# 8x8matrix.net
KiCad netlist of a schematic drawn in EAGLE
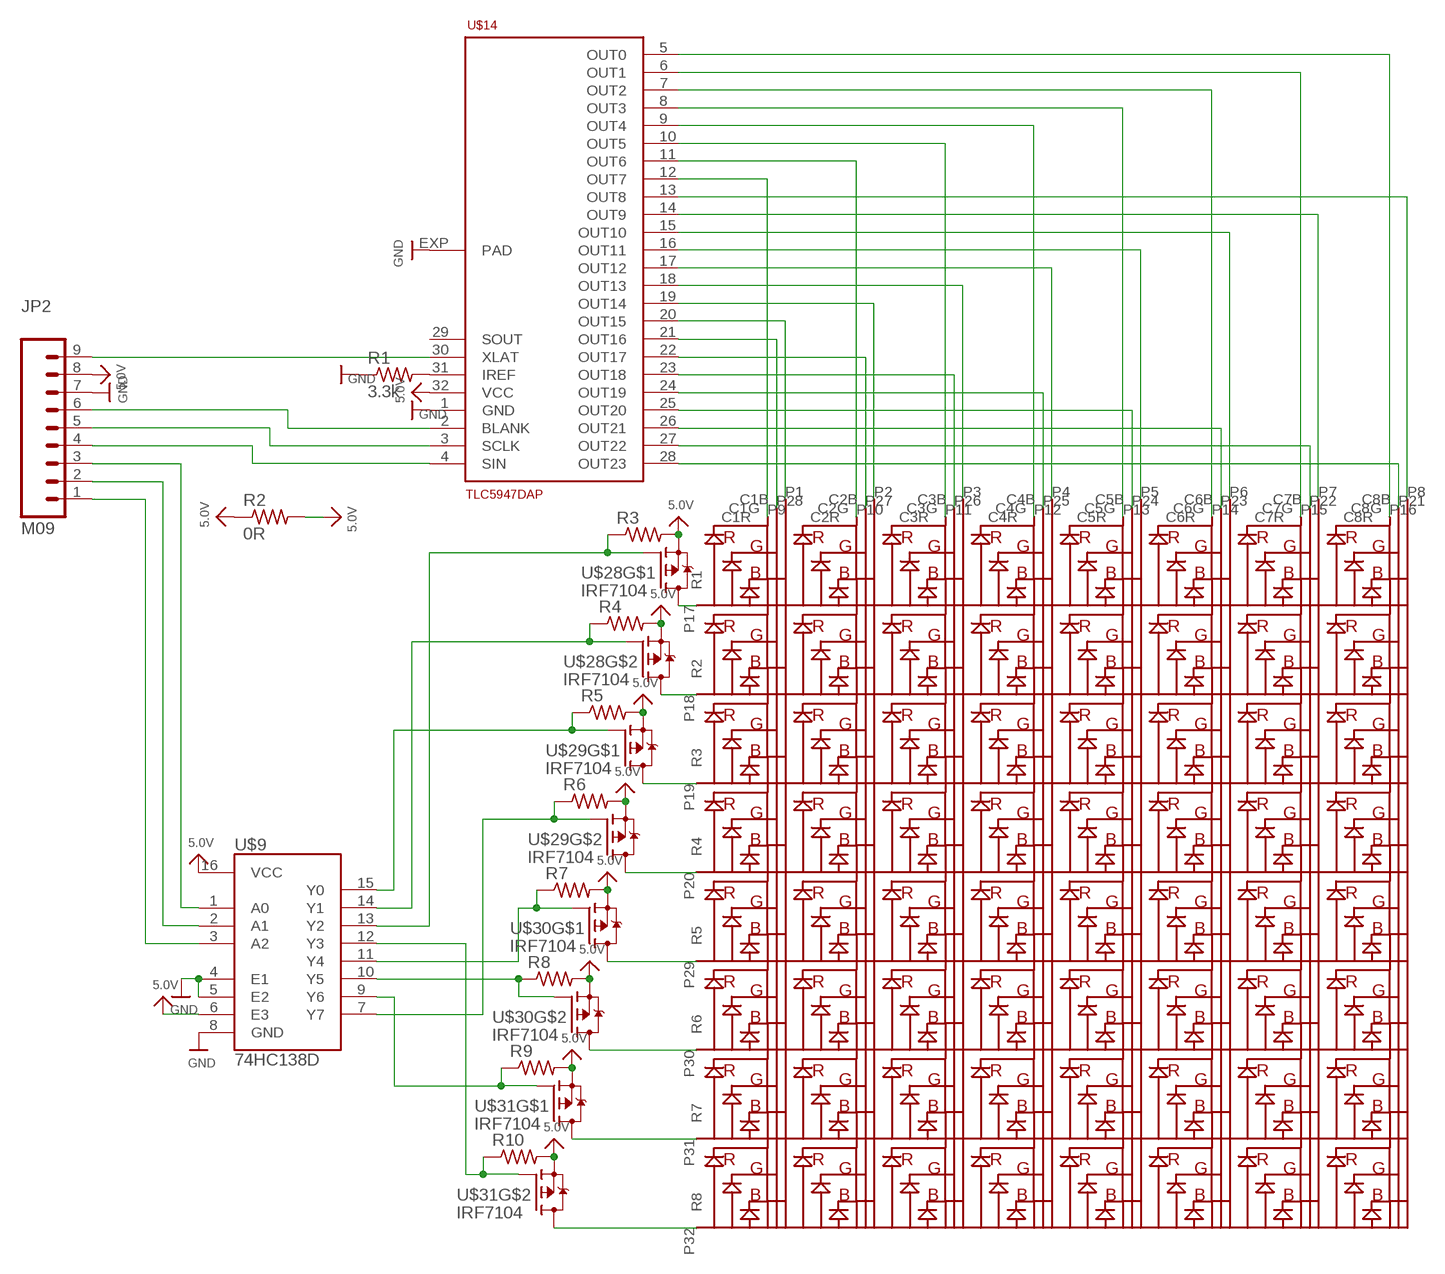
[diagram p0: schematic, sheet 1]

(export (version "E")
  (design (tool "Eeschema 10.0.6"))
  (components
    (comp (ref "JP2")
      (value "M09")
      (footprint "eagle-import:1X09")
      (libsource (lib "eagle-import") (part "M09"))
    )
    (comp (ref "R1")
      (value "3.3k")
      (footprint "eagle-import:R0805")
      (libsource (lib "eagle-import") (part "R-US_R0805"))
    )
    (comp (ref "R2")
      (value "0R")
      (footprint "eagle-import:M1206")
      (libsource (lib "eagle-import") (part "R-US_M1206"))
    )
    (comp (ref "R3")
      (value "R-US_R0805")
      (footprint "eagle-import:R0805")
      (libsource (lib "eagle-import") (part "R-US_R0805"))
    )
    (comp (ref "R4")
      (value "R-US_R0805")
      (footprint "eagle-import:R0805")
      (libsource (lib "eagle-import") (part "R-US_R0805"))
    )
    (comp (ref "R5")
      (value "R-US_R0805")
      (footprint "eagle-import:R0805")
      (libsource (lib "eagle-import") (part "R-US_R0805"))
    )
    (comp (ref "R6")
      (value "R-US_R0805")
      (footprint "eagle-import:R0805")
      (libsource (lib "eagle-import") (part "R-US_R0805"))
    )
    (comp (ref "R7")
      (value "R-US_R0805")
      (footprint "eagle-import:R0805")
      (libsource (lib "eagle-import") (part "R-US_R0805"))
    )
    (comp (ref "R8")
      (value "R-US_R0805")
      (footprint "eagle-import:R0805")
      (libsource (lib "eagle-import") (part "R-US_R0805"))
    )
    (comp (ref "R9")
      (value "R-US_R0805")
      (footprint "eagle-import:R0805")
      (libsource (lib "eagle-import") (part "R-US_R0805"))
    )
    (comp (ref "R10")
      (value "R-US_R0805")
      (footprint "eagle-import:R0805")
      (libsource (lib "eagle-import") (part "R-US_R0805"))
    )
    (comp (ref "U$1")
      (value "GTM2088ARGB")
      (footprint "eagle-import:8X8MATRIX")
      (libsource (lib "eagle-import") (part "GTM2088ARGB"))
    )
    (comp (ref "U$9")
      (value "74HC138D")
      (footprint "eagle-import:SO-16")
      (libsource (lib "eagle-import") (part "74HC138D"))
    )
    (comp (ref "U$14")
      (value "TLC5947DAP")
      (footprint "eagle-import:HTSSOP32DAP")
      (libsource (lib "eagle-import") (part "TLC5947DAP"))
    )
    (comp (ref "U$28")
      (value "IRF7104")
      (footprint "eagle-import:SOIC8")
      (libsource (lib "eagle-import") (part "IRF7104"))
    )
    (comp (ref "U$29")
      (value "IRF7104")
      (footprint "eagle-import:SOIC8")
      (libsource (lib "eagle-import") (part "IRF7104"))
    )
    (comp (ref "U$30")
      (value "IRF7104")
      (footprint "eagle-import:SOIC8")
      (libsource (lib "eagle-import") (part "IRF7104"))
    )
    (comp (ref "U$31")
      (value "IRF7104")
      (footprint "eagle-import:SOIC8")
      (libsource (lib "eagle-import") (part "IRF7104"))
    )
  )
  (nets
    (net (code "1") (name "5.0V") (class "Default")
      (node (ref "JP2") (pin "8") (pinfunction "8_8") (pintype "passive"))
      (node (ref "R10") (pin "2") (pinfunction "2_2") (pintype "passive"))
      (node (ref "R2") (pin "1") (pinfunction "1_1") (pintype "passive"))
      (node (ref "R2") (pin "2") (pinfunction "2_2") (pintype "passive"))
      (node (ref "R3") (pin "2") (pinfunction "2_2") (pintype "passive"))
      (node (ref "R4") (pin "2") (pinfunction "2_2") (pintype "passive"))
      (node (ref "R5") (pin "2") (pinfunction "2_2") (pintype "passive"))
      (node (ref "R6") (pin "2") (pinfunction "2_2") (pintype "passive"))
      (node (ref "R7") (pin "2") (pinfunction "2_2") (pintype "passive"))
      (node (ref "R8") (pin "2") (pinfunction "2_2") (pintype "passive"))
      (node (ref "R9") (pin "2") (pinfunction "2_2") (pintype "passive"))
      (node (ref "U$14") (pin "32") (pinfunction "VCC_32") (pintype "bidirectional"))
      (node (ref "U$28") (pin "1") (pinfunction "S_1") (pintype "passive"))
      (node (ref "U$28") (pin "3") (pinfunction "S_3") (pintype "passive"))
      (node (ref "U$29") (pin "1") (pinfunction "S_1") (pintype "passive"))
      (node (ref "U$29") (pin "3") (pinfunction "S_3") (pintype "passive"))
      (node (ref "U$30") (pin "1") (pinfunction "S_1") (pintype "passive"))
      (node (ref "U$30") (pin "3") (pinfunction "S_3") (pintype "passive"))
      (node (ref "U$31") (pin "1") (pinfunction "S_1") (pintype "passive"))
      (node (ref "U$31") (pin "3") (pinfunction "S_3") (pintype "passive"))
      (node (ref "U$9") (pin "16") (pinfunction "VCC_16") (pintype "bidirectional"))
      (node (ref "U$9") (pin "6") (pinfunction "E3_6") (pintype "bidirectional"))
    )
    (net (code "2") (name "GND") (class "Default")
      (node (ref "JP2") (pin "7") (pinfunction "7_7") (pintype "passive"))
      (node (ref "R1") (pin "1") (pinfunction "1_1") (pintype "passive"))
      (node (ref "U$14") (pin "1") (pinfunction "GND_1") (pintype "bidirectional"))
      (node (ref "U$14") (pin "EXP") (pinfunction "PAD_EXP") (pintype "bidirectional"))
      (node (ref "U$9") (pin "4") (pinfunction "E1_4") (pintype "bidirectional"))
      (node (ref "U$9") (pin "5") (pinfunction "E2_5") (pintype "bidirectional"))
      (node (ref "U$9") (pin "8") (pinfunction "GND_8") (pintype "bidirectional"))
    )
    (net (code "3") (name "Net-(U$1-C1B)") (class "Default")
      (node (ref "U$1") (pin "P1") (pinfunction "C1B_P1") (pintype "bidirectional"))
      (node (ref "U$14") (pin "20") (pinfunction "OUT15_20") (pintype "bidirectional"))
    )
    (net (code "4") (name "Net-(U$1-C1G)") (class "Default")
      (node (ref "U$1") (pin "P28") (pinfunction "C1G_P28") (pintype "bidirectional"))
      (node (ref "U$14") (pin "21") (pinfunction "OUT16_21") (pintype "bidirectional"))
    )
    (net (code "5") (name "Net-(U$1-C1R)") (class "Default")
      (node (ref "U$1") (pin "P9") (pinfunction "C1R_P9") (pintype "bidirectional"))
      (node (ref "U$14") (pin "12") (pinfunction "OUT7_12") (pintype "bidirectional"))
    )
    (net (code "6") (name "Net-(U$1-C2B)") (class "Default")
      (node (ref "U$1") (pin "P2") (pinfunction "C2B_P2") (pintype "bidirectional"))
      (node (ref "U$14") (pin "19") (pinfunction "OUT14_19") (pintype "bidirectional"))
    )
    (net (code "7") (name "Net-(U$1-C2G)") (class "Default")
      (node (ref "U$1") (pin "P27") (pinfunction "C2G_P27") (pintype "bidirectional"))
      (node (ref "U$14") (pin "22") (pinfunction "OUT17_22") (pintype "bidirectional"))
    )
    (net (code "8") (name "Net-(U$1-C2R)") (class "Default")
      (node (ref "U$1") (pin "P10") (pinfunction "C2R_P10") (pintype "bidirectional"))
      (node (ref "U$14") (pin "11") (pinfunction "OUT6_11") (pintype "bidirectional"))
    )
    (net (code "9") (name "Net-(U$1-C3B)") (class "Default")
      (node (ref "U$1") (pin "P3") (pinfunction "C3B_P3") (pintype "bidirectional"))
      (node (ref "U$14") (pin "18") (pinfunction "OUT13_18") (pintype "bidirectional"))
    )
    (net (code "10") (name "Net-(U$1-C3G)") (class "Default")
      (node (ref "U$1") (pin "P26") (pinfunction "C3G_P26") (pintype "bidirectional"))
      (node (ref "U$14") (pin "23") (pinfunction "OUT18_23") (pintype "bidirectional"))
    )
    (net (code "11") (name "Net-(U$1-C3R)") (class "Default")
      (node (ref "U$1") (pin "P11") (pinfunction "C3R_P11") (pintype "bidirectional"))
      (node (ref "U$14") (pin "10") (pinfunction "OUT5_10") (pintype "bidirectional"))
    )
    (net (code "12") (name "Net-(U$1-C4B)") (class "Default")
      (node (ref "U$1") (pin "P4") (pinfunction "C4B_P4") (pintype "bidirectional"))
      (node (ref "U$14") (pin "17") (pinfunction "OUT12_17") (pintype "bidirectional"))
    )
    (net (code "13") (name "Net-(U$1-C4G)") (class "Default")
      (node (ref "U$1") (pin "P25") (pinfunction "C4G_P25") (pintype "bidirectional"))
      (node (ref "U$14") (pin "24") (pinfunction "OUT19_24") (pintype "bidirectional"))
    )
    (net (code "14") (name "Net-(U$1-C4R)") (class "Default")
      (node (ref "U$1") (pin "P12") (pinfunction "C4R_P12") (pintype "bidirectional"))
      (node (ref "U$14") (pin "9") (pinfunction "OUT4_9") (pintype "bidirectional"))
    )
    (net (code "15") (name "Net-(U$1-C5B)") (class "Default")
      (node (ref "U$1") (pin "P5") (pinfunction "C5B_P5") (pintype "bidirectional"))
      (node (ref "U$14") (pin "16") (pinfunction "OUT11_16") (pintype "bidirectional"))
    )
    (net (code "16") (name "Net-(U$1-C5G)") (class "Default")
      (node (ref "U$1") (pin "P24") (pinfunction "C5G_P24") (pintype "bidirectional"))
      (node (ref "U$14") (pin "25") (pinfunction "OUT20_25") (pintype "bidirectional"))
    )
    (net (code "17") (name "Net-(U$1-C5R)") (class "Default")
      (node (ref "U$1") (pin "P13") (pinfunction "C5R_P13") (pintype "bidirectional"))
      (node (ref "U$14") (pin "8") (pinfunction "OUT3_8") (pintype "bidirectional"))
    )
    (net (code "18") (name "Net-(U$1-C6B)") (class "Default")
      (node (ref "U$1") (pin "P6") (pinfunction "C6B_P6") (pintype "bidirectional"))
      (node (ref "U$14") (pin "15") (pinfunction "OUT10_15") (pintype "bidirectional"))
    )
    (net (code "19") (name "Net-(U$1-C6G)") (class "Default")
      (node (ref "U$1") (pin "P23") (pinfunction "C6G_P23") (pintype "bidirectional"))
      (node (ref "U$14") (pin "26") (pinfunction "OUT21_26") (pintype "bidirectional"))
    )
    (net (code "20") (name "Net-(U$1-C6R)") (class "Default")
      (node (ref "U$1") (pin "P14") (pinfunction "C6R_P14") (pintype "bidirectional"))
      (node (ref "U$14") (pin "7") (pinfunction "OUT2_7") (pintype "bidirectional"))
    )
    (net (code "21") (name "Net-(U$1-C7B)") (class "Default")
      (node (ref "U$1") (pin "P7") (pinfunction "C7B_P7") (pintype "bidirectional"))
      (node (ref "U$14") (pin "14") (pinfunction "OUT9_14") (pintype "bidirectional"))
    )
    (net (code "22") (name "Net-(U$1-C7G)") (class "Default")
      (node (ref "U$1") (pin "P22") (pinfunction "C7G_P22") (pintype "bidirectional"))
      (node (ref "U$14") (pin "27") (pinfunction "OUT22_27") (pintype "bidirectional"))
    )
    (net (code "23") (name "Net-(U$1-C7R)") (class "Default")
      (node (ref "U$1") (pin "P15") (pinfunction "C7R_P15") (pintype "bidirectional"))
      (node (ref "U$14") (pin "6") (pinfunction "OUT1_6") (pintype "bidirectional"))
    )
    (net (code "24") (name "Net-(U$1-C8B)") (class "Default")
      (node (ref "U$1") (pin "P8") (pinfunction "C8B_P8") (pintype "bidirectional"))
      (node (ref "U$14") (pin "13") (pinfunction "OUT8_13") (pintype "bidirectional"))
    )
    (net (code "25") (name "Net-(U$1-C8G)") (class "Default")
      (node (ref "U$1") (pin "P21") (pinfunction "C8G_P21") (pintype "bidirectional"))
      (node (ref "U$14") (pin "28") (pinfunction "OUT23_28") (pintype "bidirectional"))
    )
    (net (code "26") (name "Net-(U$1-C8R)") (class "Default")
      (node (ref "U$1") (pin "P16") (pinfunction "C8R_P16") (pintype "bidirectional"))
      (node (ref "U$14") (pin "5") (pinfunction "OUT0_5") (pintype "bidirectional"))
    )
    (net (code "27") (name "Net-(U$1-R1)") (class "Default")
      (node (ref "U$1") (pin "P17") (pinfunction "R1_P17") (pintype "bidirectional"))
      (node (ref "U$28") (pin "7") (pinfunction "D_7") (pintype "passive"))
      (node (ref "U$28") (pin "8") (pinfunction "D_8") (pintype "passive"))
    )
    (net (code "28") (name "Net-(U$1-R2)") (class "Default")
      (node (ref "U$1") (pin "P18") (pinfunction "R2_P18") (pintype "bidirectional"))
      (node (ref "U$28") (pin "5") (pinfunction "D_5") (pintype "passive"))
      (node (ref "U$28") (pin "6") (pinfunction "D_6") (pintype "passive"))
    )
    (net (code "29") (name "Net-(U$1-R3)") (class "Default")
      (node (ref "U$1") (pin "P19") (pinfunction "R3_P19") (pintype "bidirectional"))
      (node (ref "U$29") (pin "7") (pinfunction "D_7") (pintype "passive"))
      (node (ref "U$29") (pin "8") (pinfunction "D_8") (pintype "passive"))
    )
    (net (code "30") (name "Net-(U$1-R4)") (class "Default")
      (node (ref "U$1") (pin "P20") (pinfunction "R4_P20") (pintype "bidirectional"))
      (node (ref "U$29") (pin "5") (pinfunction "D_5") (pintype "passive"))
      (node (ref "U$29") (pin "6") (pinfunction "D_6") (pintype "passive"))
    )
    (net (code "31") (name "Net-(U$1-R5)") (class "Default")
      (node (ref "U$1") (pin "P29") (pinfunction "R5_P29") (pintype "bidirectional"))
      (node (ref "U$30") (pin "7") (pinfunction "D_7") (pintype "passive"))
      (node (ref "U$30") (pin "8") (pinfunction "D_8") (pintype "passive"))
    )
    (net (code "32") (name "Net-(U$1-R6)") (class "Default")
      (node (ref "U$1") (pin "P30") (pinfunction "R6_P30") (pintype "bidirectional"))
      (node (ref "U$30") (pin "5") (pinfunction "D_5") (pintype "passive"))
      (node (ref "U$30") (pin "6") (pinfunction "D_6") (pintype "passive"))
    )
    (net (code "33") (name "Net-(U$1-R7)") (class "Default")
      (node (ref "U$1") (pin "P31") (pinfunction "R7_P31") (pintype "bidirectional"))
      (node (ref "U$31") (pin "7") (pinfunction "D_7") (pintype "passive"))
      (node (ref "U$31") (pin "8") (pinfunction "D_8") (pintype "passive"))
    )
    (net (code "34") (name "Net-(U$1-R8)") (class "Default")
      (node (ref "U$1") (pin "P32") (pinfunction "R8_P32") (pintype "bidirectional"))
      (node (ref "U$31") (pin "5") (pinfunction "D_5") (pintype "passive"))
      (node (ref "U$31") (pin "6") (pinfunction "D_6") (pintype "passive"))
    )
    (net (code "35") (name "Net-(U$9-A0)") (class "Default")
      (node (ref "JP2") (pin "3") (pinfunction "3_3") (pintype "passive"))
      (node (ref "U$9") (pin "1") (pinfunction "A0_1") (pintype "bidirectional"))
    )
    (net (code "36") (name "Net-(U$9-A1)") (class "Default")
      (node (ref "JP2") (pin "2") (pinfunction "2_2") (pintype "passive"))
      (node (ref "U$9") (pin "2") (pinfunction "A1_2") (pintype "bidirectional"))
    )
    (net (code "37") (name "Net-(U$9-A2)") (class "Default")
      (node (ref "JP2") (pin "1") (pinfunction "1_1") (pintype "passive"))
      (node (ref "U$9") (pin "3") (pinfunction "A2_3") (pintype "bidirectional"))
    )
    (net (code "38") (name "Net-(U$14-BLANK)") (class "Default")
      (node (ref "JP2") (pin "6") (pinfunction "6_6") (pintype "passive"))
      (node (ref "U$14") (pin "2") (pinfunction "BLANK_2") (pintype "bidirectional"))
    )
    (net (code "39") (name "Net-(U$14-IREF)") (class "Default")
      (node (ref "R1") (pin "2") (pinfunction "2_2") (pintype "passive"))
      (node (ref "U$14") (pin "31") (pinfunction "IREF_31") (pintype "bidirectional"))
    )
    (net (code "40") (name "Net-(U$14-SCLK)") (class "Default")
      (node (ref "JP2") (pin "5") (pinfunction "5_5") (pintype "passive"))
      (node (ref "U$14") (pin "3") (pinfunction "SCLK_3") (pintype "bidirectional"))
    )
    (net (code "41") (name "Net-(U$14-SIN)") (class "Default")
      (node (ref "JP2") (pin "4") (pinfunction "4_4") (pintype "passive"))
      (node (ref "U$14") (pin "4") (pinfunction "SIN_4") (pintype "bidirectional"))
    )
    (net (code "42") (name "Net-(U$14-XLAT)") (class "Default")
      (node (ref "JP2") (pin "9") (pinfunction "9_9") (pintype "passive"))
      (node (ref "U$14") (pin "30") (pinfunction "XLAT_30") (pintype "bidirectional"))
    )
    (net (code "43") (name "Net-(U$28A-G)") (class "Default")
      (node (ref "R3") (pin "1") (pinfunction "1_1") (pintype "passive"))
      (node (ref "U$28") (pin "2") (pinfunction "G_2") (pintype "passive"))
      (node (ref "U$9") (pin "13") (pinfunction "Y2_13") (pintype "bidirectional"))
    )
    (net (code "44") (name "Net-(U$28B-G)") (class "Default")
      (node (ref "R4") (pin "1") (pinfunction "1_1") (pintype "passive"))
      (node (ref "U$28") (pin "4") (pinfunction "G_4") (pintype "passive"))
      (node (ref "U$9") (pin "14") (pinfunction "Y1_14") (pintype "bidirectional"))
    )
    (net (code "45") (name "Net-(U$29A-G)") (class "Default")
      (node (ref "R5") (pin "1") (pinfunction "1_1") (pintype "passive"))
      (node (ref "U$29") (pin "2") (pinfunction "G_2") (pintype "passive"))
      (node (ref "U$9") (pin "15") (pinfunction "Y0_15") (pintype "bidirectional"))
    )
    (net (code "46") (name "Net-(U$29B-G)") (class "Default")
      (node (ref "R6") (pin "1") (pinfunction "1_1") (pintype "passive"))
      (node (ref "U$29") (pin "4") (pinfunction "G_4") (pintype "passive"))
      (node (ref "U$9") (pin "7") (pinfunction "Y7_7") (pintype "bidirectional"))
    )
    (net (code "47") (name "Net-(U$30A-G)") (class "Default")
      (node (ref "R7") (pin "1") (pinfunction "1_1") (pintype "passive"))
      (node (ref "U$30") (pin "2") (pinfunction "G_2") (pintype "passive"))
      (node (ref "U$9") (pin "11") (pinfunction "Y4_11") (pintype "bidirectional"))
    )
    (net (code "48") (name "Net-(U$30B-G)") (class "Default")
      (node (ref "R8") (pin "1") (pinfunction "1_1") (pintype "passive"))
      (node (ref "U$30") (pin "4") (pinfunction "G_4") (pintype "passive"))
      (node (ref "U$9") (pin "10") (pinfunction "Y5_10") (pintype "bidirectional"))
    )
    (net (code "49") (name "Net-(U$31A-G)") (class "Default")
      (node (ref "R9") (pin "1") (pinfunction "1_1") (pintype "passive"))
      (node (ref "U$31") (pin "2") (pinfunction "G_2") (pintype "passive"))
      (node (ref "U$9") (pin "9") (pinfunction "Y6_9") (pintype "bidirectional"))
    )
    (net (code "50") (name "Net-(U$31B-G)") (class "Default")
      (node (ref "R10") (pin "1") (pinfunction "1_1") (pintype "passive"))
      (node (ref "U$31") (pin "4") (pinfunction "G_4") (pintype "passive"))
      (node (ref "U$9") (pin "12") (pinfunction "Y3_12") (pintype "bidirectional"))
    )
    (net (code "51") (name "unconnected-(U$14-SOUT-Pad29)") (class "Default")
      (node (ref "U$14") (pin "29") (pinfunction "SOUT_29") (pintype "bidirectional"))
    )
  )
)
